# 38-TEST_HEADER.net
KiCad netlist of a schematic drawn in Altium Designer
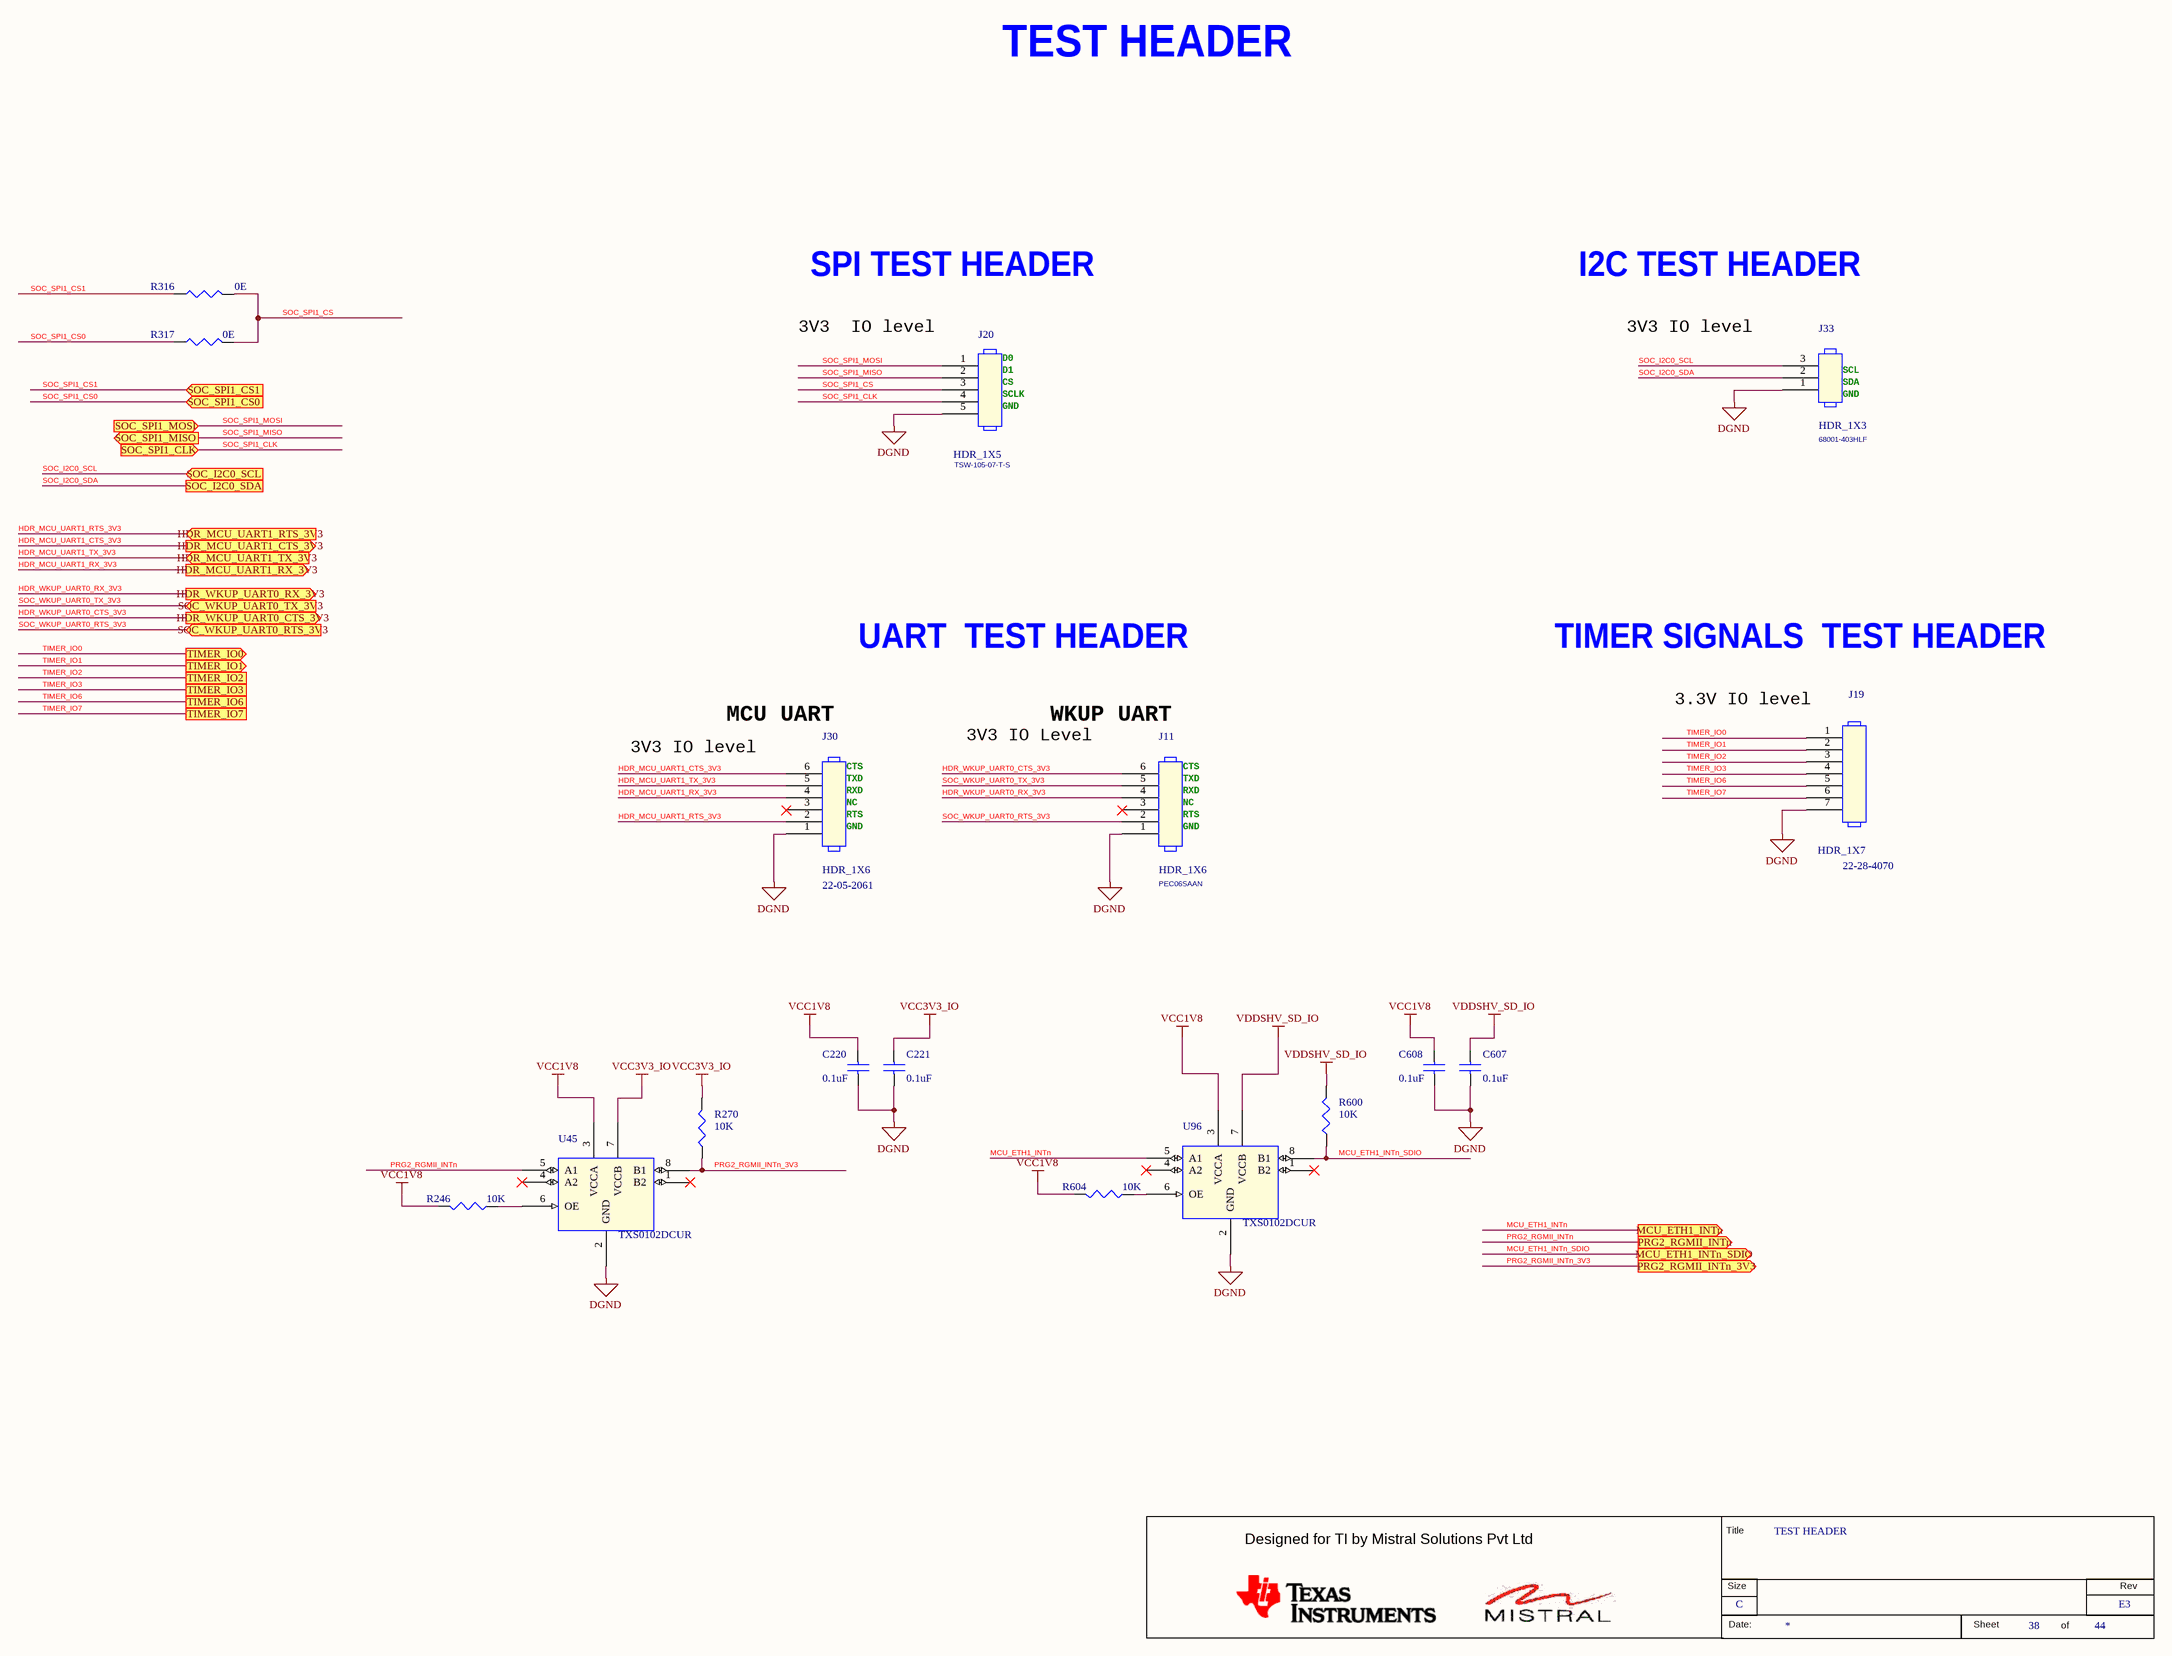
[diagram p0: 38-TEST HEADER.SchDoc]

(export (version "E")
  (design (tool "Eeschema 10.0.6"))
  (components
    (comp (ref "C220")
      (value "0.1uF")
      (footprint "CAP0201_0-5")
      (description "CAP CERAMIC 0.1uF 16V 10% X5R 0201")
      (fields (field (name "DISTRIBUTOR_PART_NUMBER") "490-16742-1-ND") (field (name "VOLTAGE") "16V"))
      (libsource (lib "*") (part "CAP_Dup5"))
    )
    (comp (ref "C221")
      (value "0.1uF")
      (footprint "CAP0201_0-5")
      (description "CAP CERAMIC 0.1uF 16V 10% X5R 0201")
      (fields
        (field (name "MISTRAL PART NO") "120009030072-R")
        (field (name "MFR_PART_NUMBER") "GRM033R61C104KE84J")
      )
      (libsource (lib "*") (part "CAP_Dup5"))
    )
    (comp (ref "C607")
      (value "0.1uF")
      (footprint "CAP0201_0-5")
      (description "CAP CERAMIC 0.1uF 16V 10% X5R 0201")
      (fields
        (field (name "MISTRAL PART NO") "120009030072-R")
        (field (name "MFR_PART_NUMBER") "GRM033R61C104KE84J")
      )
      (libsource (lib "*") (part "CAP_Dup5"))
    )
    (comp (ref "C608")
      (value "0.1uF")
      (footprint "CAP0201_0-5")
      (description "CAP CERAMIC 0.1uF 16V 10% X5R 0201")
      (fields (field (name "DISTRIBUTOR_PART_NUMBER") "490-16742-1-ND") (field (name "VOLTAGE") "16V"))
      (libsource (lib "*") (part "CAP_Dup5"))
    )
    (comp (ref "J11")
      (value "HDR_1X6")
      (footprint "HDR_6X1_100_S_T")
      (description "HDR 1X6 2.54 PITCH ST TH")
      (fields
        (field (name "MISTRAL PART NO") "150016060022-R")
        (field (name "MFR_PART_NUMBER") "PEC06SAAN")
        (field (name "TOLERANCE") "NA")
      )
      (libsource (lib "*") (part "HEADER_6X1"))
    )
    (comp (ref "J19")
      (value "HDR_1X7")
      (footprint "HDR_1X7_22284070_S_T_8-4")
      (description "CON HDR 1X7 2.54MM PITCH ST TH")
      (fields
        (field (name "DISTRIBUTOR_PART_NUMBER") "WM50014-07-ND")
        (field (name "VOLTAGE") "NA")
        (field (name "MFR_PART_NUMBER") "22-28-4070")
      )
      (libsource (lib "*") (part "HEADER_7X1"))
    )
    (comp (ref "J20")
      (value "HDR_1X5")
      (footprint "HDR_5X1_100_S_T_8-4")
      (description "CON HDR 1X5 2.54MM PITCH ST TH")
      (fields
        (field (name "DISTRIBUTOR_PART_NUMBER") "SAM1035-05-ND")
        (field (name "VOLTAGE") "NA")
        (field (name "MFR_PART_NUMBER") "TSW-105-07-T-S")
      )
      (libsource (lib "*") (part "HEADER_5X1"))
    )
    (comp (ref "J30")
      (value "HDR_1X6")
      (footprint "HDR_1X6_22052061_R_T_6-3")
      (description "CON HDR 1X6 2.54MM PITCH RT TH")
      (fields
        (field (name "MISTRAL PART NO") "150018010023-R")
        (field (name "MFR_PART_NUMBER") "22-05-2061")
        (field (name "TOLERANCE") "NA")
      )
      (libsource (lib "*") (part "HEADER_6X1"))
    )
    (comp (ref "J33")
      (value "HDR_1X3")
      (footprint "HDR_3X1_100_S_T")
      (description "HDR 1X3 2.54MM PITCH ST TH")
      (fields
        (field (name "DISTRIBUTOR_PART_NUMBER") "609-3471-ND")
        (field (name "VOLTAGE") "NA")
        (field (name "MFR_PART_NUMBER") "68001-403HLF")
      )
      (libsource (lib "*") (part "HEADER_3X1"))
    )
    (comp (ref "R246")
      (value "10K")
      (footprint "RES0402_0-5")
      (description "RES 10K 1/16W 5% 0402")
      (fields (field (name "DISTRIBUTOR_PART_NUMBER") "311-10KJRCT-ND") (field (name "VOLTAGE") "NA"))
      (libsource (lib "*") (part "RESISTOR_Dup5"))
    )
    (comp (ref "R270")
      (value "10K")
      (footprint "RES0402_0-5")
      (description "RES 10K 1/16W 5% 0402")
      (fields (field (name "DISTRIBUTOR_PART_NUMBER") "311-10KJRCT-ND") (field (name "VOLTAGE") "NA"))
      (libsource (lib "*") (part "RESISTOR_Dup5"))
    )
    (comp (ref "R316")
      (value "0E")
      (footprint "RES0402_0-5")
      (description "RES 0E 1/16W 0402")
      (fields (field (name "DISTRIBUTOR_PART_NUMBER") "541-0.0JCT-ND") (field (name "VOLTAGE") "NA"))
      (libsource (lib "*") (part "RESISTOR_Dup4"))
    )
    (comp (ref "R317")
      (value "0E")
      (footprint "RES0402_0-5")
      (description "RES 0E 1/16W 0402")
      (fields
        (field (name "MISTRAL PART NO") "110010080019-P")
        (field (name "MFR_PART_NUMBER") "CRCW04020000Z0ED")
      )
      (libsource (lib "*") (part "RESISTOR_Dup4"))
    )
    (comp (ref "R600")
      (value "10K")
      (footprint "RES0402_0-5")
      (description "RES 10K 1/16W 5% 0402")
      (fields
        (field (name "MISTRAL PART NO") "110009030208-R")
        (field (name "MFR_PART_NUMBER") "RC0402JR-0710KL")
      )
      (libsource (lib "*") (part "RESISTOR_Dup5"))
    )
    (comp (ref "R604")
      (value "10K")
      (footprint "RES0402_0-5")
      (description "RES 10K 1/16W 5% 0402")
      (fields (field (name "DISTRIBUTOR_PART_NUMBER") "311-10KJRCT-ND") (field (name "VOLTAGE") "NA"))
      (libsource (lib "*") (part "RESISTOR_Dup5"))
    )
    (comp (ref "U45")
      (value "TXS0102DCUR")
      (footprint "VSSOP8_19-68_85X95_0-9")
      (description "IC 2BIT BI-DIR VOLTAGE-LEVEL TRANSLATOR US8(VSSOP8)")
      (fields
        (field (name "MISTRAL PART NO") "141009030376-R")
        (field (name "TOLERANCE") "NA")
        (field (name "LIBRARY PATH") "Y~{:}MIS_DATABAS~{E}Librar~{y}ALTIUM_TOO~{L}SCHEMATICS_PART~{S}MS_MISCINTERFACE_Library.schlib")
      )
      (libsource (lib "*") (part "TXS0102DCUR_VSSOP8"))
    )
    (comp (ref "U96")
      (value "TXS0102DCUR")
      (footprint "VSSOP8_19-68_85X95_0-9")
      (description "IC 2BIT BI-DIR VOLTAGE-LEVEL TRANSLATOR US8(VSSOP8)")
      (fields
        (field (name "MISTRAL PART NO") "141009030376-R")
        (field (name "TOLERANCE") "NA")
        (field (name "LIBRARY PATH") "Y~{:}MIS_DATABAS~{E}Librar~{y}ALTIUM_TOO~{L}SCHEMATICS_PART~{S}MS_MISCINTERFACE_Library.schlib")
      )
      (libsource (lib "*") (part "TXS0102DCUR_VSSOP8"))
    )
  )
  (nets
    (net (code "1") (name "/HDR_MCU_UART1_CTS_3V3") (class "Default")
      (node (ref "J30") (pin "6") (pinfunction "6_6") (pintype "passive"))
    )
    (net (code "2") (name "/HDR_MCU_UART1_RTS_3V3") (class "Default")
      (node (ref "J30") (pin "2") (pinfunction "2_2") (pintype "passive"))
    )
    (net (code "3") (name "/HDR_MCU_UART1_RX_3V3") (class "Default")
      (node (ref "J30") (pin "4") (pinfunction "4_4") (pintype "passive"))
    )
    (net (code "4") (name "/HDR_MCU_UART1_TX_3V3") (class "Default")
      (node (ref "J30") (pin "5") (pinfunction "5_5") (pintype "passive"))
    )
    (net (code "5") (name "/HDR_WKUP_UART0_CTS_3V3") (class "Default")
      (node (ref "J11") (pin "6") (pinfunction "6_6") (pintype "passive"))
    )
    (net (code "6") (name "/HDR_WKUP_UART0_RX_3V3") (class "Default")
      (node (ref "J11") (pin "4") (pinfunction "4_4") (pintype "passive"))
    )
    (net (code "7") (name "/MCU_ETH1_INTn") (class "Default")
      (node (ref "U96") (pin "5") (pinfunction "A1_5") (pintype "bidirectional"))
    )
    (net (code "8") (name "/MCU_ETH1_INTn_SDIO") (class "Default")
      (node (ref "R600") (pin "1") (pinfunction "1_1") (pintype "passive"))
      (node (ref "U96") (pin "8") (pinfunction "B1_8") (pintype "bidirectional"))
    )
    (net (code "9") (name "/PRG2_RGMII_INTn") (class "Default")
      (node (ref "U45") (pin "5") (pinfunction "A1_5") (pintype "bidirectional"))
    )
    (net (code "10") (name "/PRG2_RGMII_INTn_3V3") (class "Default")
      (node (ref "R270") (pin "1") (pinfunction "1_1") (pintype "passive"))
      (node (ref "U45") (pin "8") (pinfunction "B1_8") (pintype "bidirectional"))
    )
    (net (code "11") (name "/SOC_I2C0_SCL") (class "Default")
      (node (ref "J33") (pin "3") (pinfunction "3_3") (pintype "passive"))
    )
    (net (code "12") (name "/SOC_I2C0_SDA") (class "Default")
      (node (ref "J33") (pin "2") (pinfunction "2_2") (pintype "passive"))
    )
    (net (code "13") (name "/SOC_SPI1_CLK") (class "Default")
      (node (ref "J20") (pin "4") (pinfunction "4_4") (pintype "passive"))
    )
    (net (code "14") (name "/SOC_SPI1_CS") (class "Default")
      (node (ref "J20") (pin "3") (pinfunction "3_3") (pintype "passive"))
      (node (ref "R316") (pin "1") (pinfunction "1_1") (pintype "passive"))
      (node (ref "R317") (pin "1") (pinfunction "1_1") (pintype "passive"))
    )
    (net (code "15") (name "/SOC_SPI1_CS0") (class "Default")
      (node (ref "R317") (pin "2") (pinfunction "2_2") (pintype "passive"))
    )
    (net (code "16") (name "/SOC_SPI1_CS1") (class "Default")
      (node (ref "R316") (pin "2") (pinfunction "2_2") (pintype "passive"))
    )
    (net (code "17") (name "/SOC_SPI1_MISO") (class "Default")
      (node (ref "J20") (pin "2") (pinfunction "2_2") (pintype "passive"))
    )
    (net (code "18") (name "/SOC_SPI1_MOSI") (class "Default")
      (node (ref "J20") (pin "1") (pinfunction "1_1") (pintype "passive"))
    )
    (net (code "19") (name "/SOC_WKUP_UART0_RTS_3V3") (class "Default")
      (node (ref "J11") (pin "2") (pinfunction "2_2") (pintype "passive"))
    )
    (net (code "20") (name "/SOC_WKUP_UART0_TX_3V3") (class "Default")
      (node (ref "J11") (pin "5") (pinfunction "5_5") (pintype "passive"))
    )
    (net (code "21") (name "/TIMER_IO0") (class "Default")
      (node (ref "J19") (pin "1") (pinfunction "1_1") (pintype "passive"))
    )
    (net (code "22") (name "/TIMER_IO1") (class "Default")
      (node (ref "J19") (pin "2") (pinfunction "2_2") (pintype "passive"))
    )
    (net (code "23") (name "/TIMER_IO2") (class "Default")
      (node (ref "J19") (pin "3") (pinfunction "3_3") (pintype "passive"))
    )
    (net (code "24") (name "/TIMER_IO3") (class "Default")
      (node (ref "J19") (pin "4") (pinfunction "4_4") (pintype "passive"))
    )
    (net (code "25") (name "/TIMER_IO6") (class "Default")
      (node (ref "J19") (pin "5") (pinfunction "5_5") (pintype "passive"))
    )
    (net (code "26") (name "/TIMER_IO7") (class "Default")
      (node (ref "J19") (pin "6") (pinfunction "6_6") (pintype "passive"))
    )
    (net (code "27") (name "DGND") (class "Default")
      (node (ref "C220") (pin "2") (pinfunction "2_2") (pintype "passive"))
      (node (ref "C221") (pin "2") (pinfunction "2_2") (pintype "passive"))
      (node (ref "C607") (pin "2") (pinfunction "2_2") (pintype "passive"))
      (node (ref "C608") (pin "2") (pinfunction "2_2") (pintype "passive"))
      (node (ref "J11") (pin "1") (pinfunction "1_1") (pintype "passive"))
      (node (ref "J19") (pin "7") (pinfunction "7_7") (pintype "passive"))
      (node (ref "J20") (pin "5") (pinfunction "5_5") (pintype "passive"))
      (node (ref "J30") (pin "1") (pinfunction "1_1") (pintype "passive"))
      (node (ref "J33") (pin "1") (pinfunction "1_1") (pintype "passive"))
      (node (ref "U45") (pin "2") (pinfunction "GND_2") (pintype "power_in"))
      (node (ref "U96") (pin "2") (pinfunction "GND_2") (pintype "power_in"))
    )
    (net (code "28") (name "Net-(U45-OE)") (class "Default")
      (node (ref "R246") (pin "1") (pinfunction "1_1") (pintype "passive"))
      (node (ref "U45") (pin "6") (pinfunction "OE_6") (pintype "input"))
    )
    (net (code "29") (name "Net-(U96-OE)") (class "Default")
      (node (ref "R604") (pin "1") (pinfunction "1_1") (pintype "passive"))
      (node (ref "U96") (pin "6") (pinfunction "OE_6") (pintype "input"))
    )
    (net (code "30") (name "VCC1V8") (class "Default")
      (node (ref "C220") (pin "1") (pinfunction "1_1") (pintype "passive"))
      (node (ref "C608") (pin "1") (pinfunction "1_1") (pintype "passive"))
      (node (ref "R246") (pin "2") (pinfunction "2_2") (pintype "passive"))
      (node (ref "R604") (pin "2") (pinfunction "2_2") (pintype "passive"))
      (node (ref "U45") (pin "3") (pinfunction "VCCA_3") (pintype "power_in"))
      (node (ref "U96") (pin "3") (pinfunction "VCCA_3") (pintype "power_in"))
    )
    (net (code "31") (name "VCC3V3_IO") (class "Default")
      (node (ref "C221") (pin "1") (pinfunction "1_1") (pintype "passive"))
      (node (ref "R270") (pin "2") (pinfunction "2_2") (pintype "passive"))
      (node (ref "U45") (pin "7") (pinfunction "VCCB_7") (pintype "power_in"))
    )
    (net (code "32") (name "VDDSHV_SD_IO") (class "Default")
      (node (ref "C607") (pin "1") (pinfunction "1_1") (pintype "passive"))
      (node (ref "R600") (pin "2") (pinfunction "2_2") (pintype "passive"))
      (node (ref "U96") (pin "7") (pinfunction "VCCB_7") (pintype "power_in"))
    )
    (net (code "33") (name "unconnected-(J11-Pad3)") (class "Default")
      (node (ref "J11") (pin "3") (pinfunction "3_3") (pintype "passive+no_connect"))
    )
    (net (code "34") (name "unconnected-(J30-Pad3)") (class "Default")
      (node (ref "J30") (pin "3") (pinfunction "3_3") (pintype "passive+no_connect"))
    )
    (net (code "35") (name "unconnected-(U45-A2-Pad4)") (class "Default")
      (node (ref "U45") (pin "4") (pinfunction "A2_4") (pintype "bidirectional+no_connect"))
    )
    (net (code "36") (name "unconnected-(U45-B2-Pad1)") (class "Default")
      (node (ref "U45") (pin "1") (pinfunction "B2_1") (pintype "bidirectional+no_connect"))
    )
    (net (code "37") (name "unconnected-(U96-A2-Pad4)") (class "Default")
      (node (ref "U96") (pin "4") (pinfunction "A2_4") (pintype "bidirectional+no_connect"))
    )
    (net (code "38") (name "unconnected-(U96-B2-Pad1)") (class "Default")
      (node (ref "U96") (pin "1") (pinfunction "B2_1") (pintype "bidirectional+no_connect"))
    )
  )
)
